# KeyboardMoudle2.net
KiCad netlist of a schematic drawn in Altium Designer
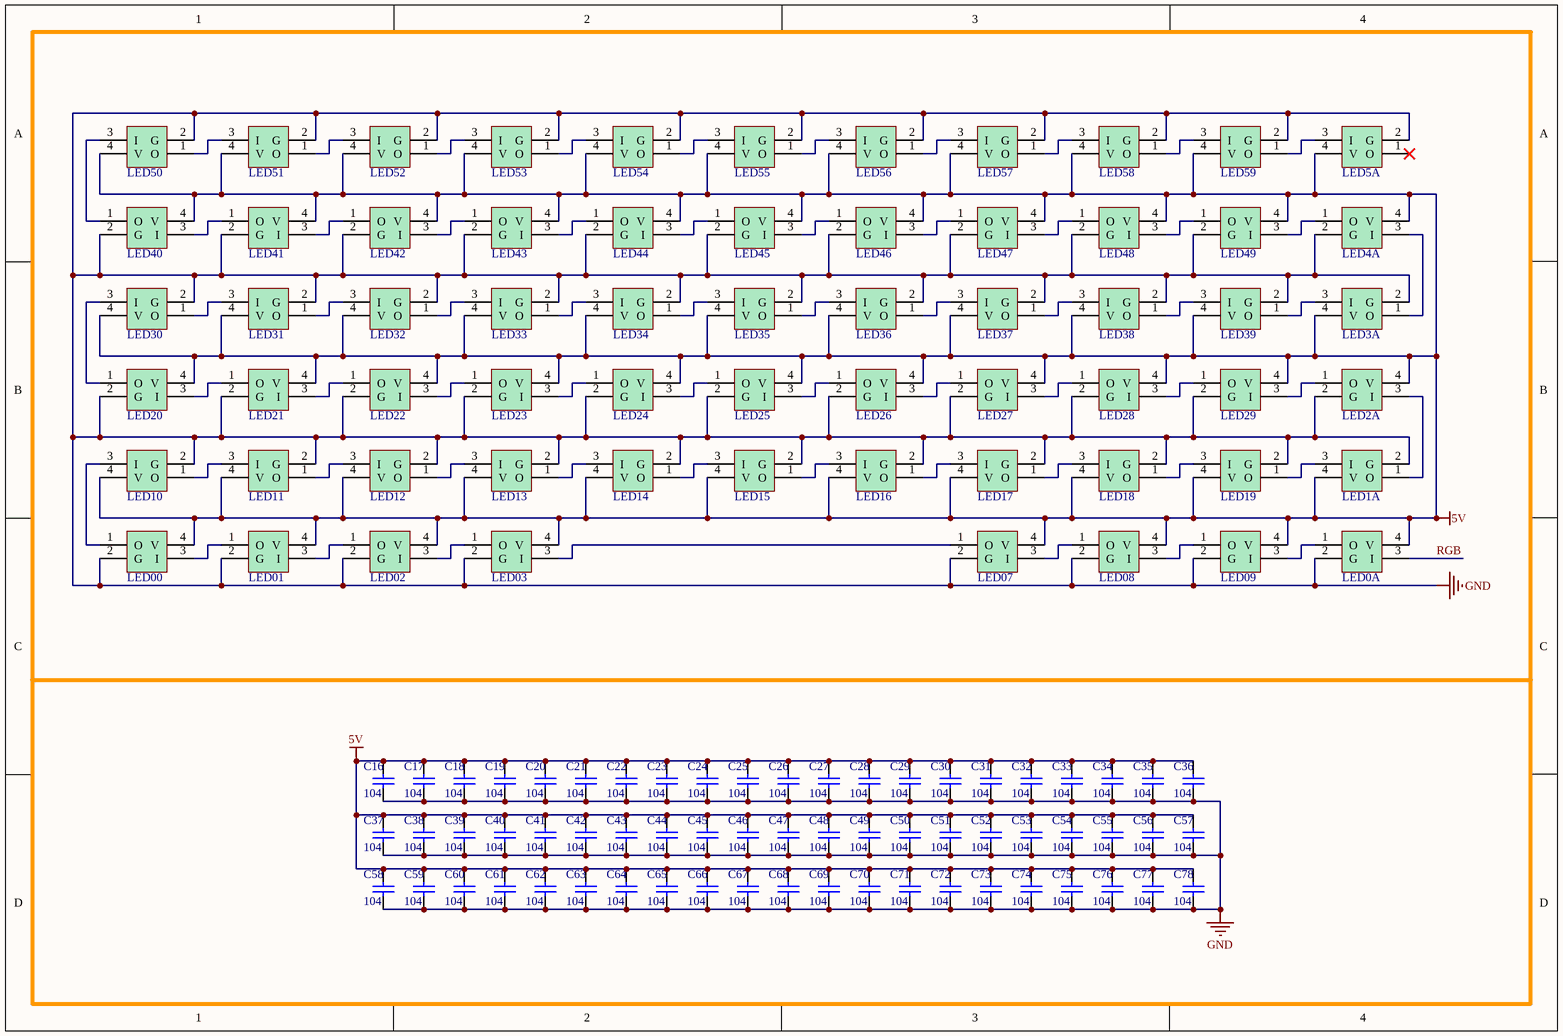
[diagram p0: KeyboardMoudle2.SchDoc]

(export (version "E")
  (design (tool "Eeschema 10.0.6"))
  (components
    (comp (ref "C16")
      (value "104")
      (footprint "0603")
      (description "贴片电容 0603")
      (libsource (lib "MT_Device") (part "CAP_0603"))
    )
    (comp (ref "C17")
      (value "104")
      (footprint "0603")
      (description "贴片电容 0603")
      (libsource (lib "MT_Device") (part "CAP_0603"))
    )
    (comp (ref "C18")
      (value "104")
      (footprint "0603")
      (description "贴片电容 0603")
      (libsource (lib "MT_Device") (part "CAP_0603"))
    )
    (comp (ref "C19")
      (value "104")
      (footprint "0603")
      (description "贴片电容 0603")
      (libsource (lib "MT_Device") (part "CAP_0603"))
    )
    (comp (ref "C20")
      (value "104")
      (footprint "0603")
      (description "贴片电容 0603")
      (libsource (lib "MT_Device") (part "CAP_0603"))
    )
    (comp (ref "C21")
      (value "104")
      (footprint "0603")
      (description "贴片电容 0603")
      (libsource (lib "MT_Device") (part "CAP_0603"))
    )
    (comp (ref "C22")
      (value "104")
      (footprint "0603")
      (description "贴片电容 0603")
      (libsource (lib "MT_Device") (part "CAP_0603"))
    )
    (comp (ref "C23")
      (value "104")
      (footprint "0603")
      (description "贴片电容 0603")
      (libsource (lib "MT_Device") (part "CAP_0603"))
    )
    (comp (ref "C24")
      (value "104")
      (footprint "0603")
      (description "贴片电容 0603")
      (libsource (lib "MT_Device") (part "CAP_0603"))
    )
    (comp (ref "C25")
      (value "104")
      (footprint "0603")
      (description "贴片电容 0603")
      (libsource (lib "MT_Device") (part "CAP_0603"))
    )
    (comp (ref "C26")
      (value "104")
      (footprint "0603")
      (description "贴片电容 0603")
      (libsource (lib "MT_Device") (part "CAP_0603"))
    )
    (comp (ref "C27")
      (value "104")
      (footprint "0603")
      (description "贴片电容 0603")
      (libsource (lib "MT_Device") (part "CAP_0603"))
    )
    (comp (ref "C28")
      (value "104")
      (footprint "0603")
      (description "贴片电容 0603")
      (libsource (lib "MT_Device") (part "CAP_0603"))
    )
    (comp (ref "C29")
      (value "104")
      (footprint "0603")
      (description "贴片电容 0603")
      (libsource (lib "MT_Device") (part "CAP_0603"))
    )
    (comp (ref "C30")
      (value "104")
      (footprint "0603")
      (description "贴片电容 0603")
      (libsource (lib "MT_Device") (part "CAP_0603"))
    )
    (comp (ref "C31")
      (value "104")
      (footprint "0603")
      (description "贴片电容 0603")
      (libsource (lib "MT_Device") (part "CAP_0603"))
    )
    (comp (ref "C32")
      (value "104")
      (footprint "0603")
      (description "贴片电容 0603")
      (libsource (lib "MT_Device") (part "CAP_0603"))
    )
    (comp (ref "C33")
      (value "104")
      (footprint "0603")
      (description "贴片电容 0603")
      (libsource (lib "MT_Device") (part "CAP_0603"))
    )
    (comp (ref "C34")
      (value "104")
      (footprint "0603")
      (description "贴片电容 0603")
      (libsource (lib "MT_Device") (part "CAP_0603"))
    )
    (comp (ref "C35")
      (value "104")
      (footprint "0603")
      (description "贴片电容 0603")
      (libsource (lib "MT_Device") (part "CAP_0603"))
    )
    (comp (ref "C36")
      (value "104")
      (footprint "0603")
      (description "贴片电容 0603")
      (libsource (lib "MT_Device") (part "CAP_0603"))
    )
    (comp (ref "C37")
      (value "104")
      (footprint "0603")
      (description "贴片电容 0603")
      (libsource (lib "MT_Device") (part "CAP_0603"))
    )
    (comp (ref "C38")
      (value "104")
      (footprint "0603")
      (description "贴片电容 0603")
      (libsource (lib "MT_Device") (part "CAP_0603"))
    )
    (comp (ref "C39")
      (value "104")
      (footprint "0603")
      (description "贴片电容 0603")
      (libsource (lib "MT_Device") (part "CAP_0603"))
    )
    (comp (ref "C40")
      (value "104")
      (footprint "0603")
      (description "贴片电容 0603")
      (libsource (lib "MT_Device") (part "CAP_0603"))
    )
    (comp (ref "C41")
      (value "104")
      (footprint "0603")
      (description "贴片电容 0603")
      (libsource (lib "MT_Device") (part "CAP_0603"))
    )
    (comp (ref "C42")
      (value "104")
      (footprint "0603")
      (description "贴片电容 0603")
      (libsource (lib "MT_Device") (part "CAP_0603"))
    )
    (comp (ref "C43")
      (value "104")
      (footprint "0603")
      (description "贴片电容 0603")
      (libsource (lib "MT_Device") (part "CAP_0603"))
    )
    (comp (ref "C44")
      (value "104")
      (footprint "0603")
      (description "贴片电容 0603")
      (libsource (lib "MT_Device") (part "CAP_0603"))
    )
    (comp (ref "C45")
      (value "104")
      (footprint "0603")
      (description "贴片电容 0603")
      (libsource (lib "MT_Device") (part "CAP_0603"))
    )
    (comp (ref "C46")
      (value "104")
      (footprint "0603")
      (description "贴片电容 0603")
      (libsource (lib "MT_Device") (part "CAP_0603"))
    )
    (comp (ref "C47")
      (value "104")
      (footprint "0603")
      (description "贴片电容 0603")
      (libsource (lib "MT_Device") (part "CAP_0603"))
    )
    (comp (ref "C48")
      (value "104")
      (footprint "0603")
      (description "贴片电容 0603")
      (libsource (lib "MT_Device") (part "CAP_0603"))
    )
    (comp (ref "C49")
      (value "104")
      (footprint "0603")
      (description "贴片电容 0603")
      (libsource (lib "MT_Device") (part "CAP_0603"))
    )
    (comp (ref "C50")
      (value "104")
      (footprint "0603")
      (description "贴片电容 0603")
      (libsource (lib "MT_Device") (part "CAP_0603"))
    )
    (comp (ref "C51")
      (value "104")
      (footprint "0603")
      (description "贴片电容 0603")
      (libsource (lib "MT_Device") (part "CAP_0603"))
    )
    (comp (ref "C52")
      (value "104")
      (footprint "0603")
      (description "贴片电容 0603")
      (libsource (lib "MT_Device") (part "CAP_0603"))
    )
    (comp (ref "C53")
      (value "104")
      (footprint "0603")
      (description "贴片电容 0603")
      (libsource (lib "MT_Device") (part "CAP_0603"))
    )
    (comp (ref "C54")
      (value "104")
      (footprint "0603")
      (description "贴片电容 0603")
      (libsource (lib "MT_Device") (part "CAP_0603"))
    )
    (comp (ref "C55")
      (value "104")
      (footprint "0603")
      (description "贴片电容 0603")
      (libsource (lib "MT_Device") (part "CAP_0603"))
    )
    (comp (ref "C56")
      (value "104")
      (footprint "0603")
      (description "贴片电容 0603")
      (libsource (lib "MT_Device") (part "CAP_0603"))
    )
    (comp (ref "C57")
      (value "104")
      (footprint "0603")
      (description "贴片电容 0603")
      (libsource (lib "MT_Device") (part "CAP_0603"))
    )
    (comp (ref "C58")
      (value "104")
      (footprint "0603")
      (description "贴片电容 0603")
      (libsource (lib "MT_Device") (part "CAP_0603"))
    )
    (comp (ref "C59")
      (value "104")
      (footprint "0603")
      (description "贴片电容 0603")
      (libsource (lib "MT_Device") (part "CAP_0603"))
    )
    (comp (ref "C60")
      (value "104")
      (footprint "0603")
      (description "贴片电容 0603")
      (libsource (lib "MT_Device") (part "CAP_0603"))
    )
    (comp (ref "C61")
      (value "104")
      (footprint "0603")
      (description "贴片电容 0603")
      (libsource (lib "MT_Device") (part "CAP_0603"))
    )
    (comp (ref "C62")
      (value "104")
      (footprint "0603")
      (description "贴片电容 0603")
      (libsource (lib "MT_Device") (part "CAP_0603"))
    )
    (comp (ref "C63")
      (value "104")
      (footprint "0603")
      (description "贴片电容 0603")
      (libsource (lib "MT_Device") (part "CAP_0603"))
    )
    (comp (ref "C64")
      (value "104")
      (footprint "0603")
      (description "贴片电容 0603")
      (libsource (lib "MT_Device") (part "CAP_0603"))
    )
    (comp (ref "C65")
      (value "104")
      (footprint "0603")
      (description "贴片电容 0603")
      (libsource (lib "MT_Device") (part "CAP_0603"))
    )
    (comp (ref "C66")
      (value "104")
      (footprint "0603")
      (description "贴片电容 0603")
      (libsource (lib "MT_Device") (part "CAP_0603"))
    )
    (comp (ref "C67")
      (value "104")
      (footprint "0603")
      (description "贴片电容 0603")
      (libsource (lib "MT_Device") (part "CAP_0603"))
    )
    (comp (ref "C68")
      (value "104")
      (footprint "0603")
      (description "贴片电容 0603")
      (libsource (lib "MT_Device") (part "CAP_0603"))
    )
    (comp (ref "C69")
      (value "104")
      (footprint "0603")
      (description "贴片电容 0603")
      (libsource (lib "MT_Device") (part "CAP_0603"))
    )
    (comp (ref "C70")
      (value "104")
      (footprint "0603")
      (description "贴片电容 0603")
      (libsource (lib "MT_Device") (part "CAP_0603"))
    )
    (comp (ref "C71")
      (value "104")
      (footprint "0603")
      (description "贴片电容 0603")
      (libsource (lib "MT_Device") (part "CAP_0603"))
    )
    (comp (ref "C72")
      (value "104")
      (footprint "0603")
      (description "贴片电容 0603")
      (libsource (lib "MT_Device") (part "CAP_0603"))
    )
    (comp (ref "C73")
      (value "104")
      (footprint "0603")
      (description "贴片电容 0603")
      (libsource (lib "MT_Device") (part "CAP_0603"))
    )
    (comp (ref "C74")
      (value "104")
      (footprint "0603")
      (description "贴片电容 0603")
      (libsource (lib "MT_Device") (part "CAP_0603"))
    )
    (comp (ref "C75")
      (value "104")
      (footprint "0603")
      (description "贴片电容 0603")
      (libsource (lib "MT_Device") (part "CAP_0603"))
    )
    (comp (ref "C76")
      (value "104")
      (footprint "0603")
      (description "贴片电容 0603")
      (libsource (lib "MT_Device") (part "CAP_0603"))
    )
    (comp (ref "C77")
      (value "104")
      (footprint "0603")
      (description "贴片电容 0603")
      (libsource (lib "MT_Device") (part "CAP_0603"))
    )
    (comp (ref "C78")
      (value "104")
      (footprint "0603")
      (description "贴片电容 0603")
      (libsource (lib "MT_Device") (part "CAP_0603"))
    )
    (comp (ref "LED00")
      (value "WS2812")
      (footprint "LED_WS2812_2020")
      (description "WS2812 LED")
      (libsource (lib "") (part "LED_WS2812_2020_1"))
    )
    (comp (ref "LED0A")
      (value "WS2812")
      (footprint "LED_WS2812_2020")
      (description "WS2812 LED")
      (libsource (lib "") (part "LED_WS2812_2020_1"))
    )
    (comp (ref "LED01")
      (value "WS2812")
      (footprint "LED_WS2812_2020")
      (description "WS2812 LED")
      (libsource (lib "") (part "LED_WS2812_2020_1"))
    )
    (comp (ref "LED1A")
      (value "WS2812")
      (footprint "LED_WS2812_2020")
      (description "WS2812 LED")
      (libsource (lib "MT_Device") (part "LED_WS2812_2020"))
    )
    (comp (ref "LED02")
      (value "WS2812")
      (footprint "LED_WS2812_2020")
      (description "WS2812 LED")
      (libsource (lib "") (part "LED_WS2812_2020_1"))
    )
    (comp (ref "LED2A")
      (value "WS2812")
      (footprint "LED_WS2812_2020")
      (description "WS2812 LED")
      (libsource (lib "") (part "LED_WS2812_2020_1"))
    )
    (comp (ref "LED03")
      (value "WS2812")
      (footprint "LED_WS2812_2020")
      (description "WS2812 LED")
      (libsource (lib "") (part "LED_WS2812_2020_1"))
    )
    (comp (ref "LED3A")
      (value "WS2812")
      (footprint "LED_WS2812_2020")
      (description "WS2812 LED")
      (libsource (lib "MT_Device") (part "LED_WS2812_2020"))
    )
    (comp (ref "LED4A")
      (value "WS2812")
      (footprint "LED_WS2812_2020")
      (description "WS2812 LED")
      (libsource (lib "") (part "LED_WS2812_2020_1"))
    )
    (comp (ref "LED5A")
      (value "WS2812")
      (footprint "LED_WS2812_2020")
      (description "WS2812 LED")
      (libsource (lib "MT_Device") (part "LED_WS2812_2020"))
    )
    (comp (ref "LED07")
      (value "WS2812")
      (footprint "LED_WS2812_2020")
      (description "WS2812 LED")
      (libsource (lib "") (part "LED_WS2812_2020_1"))
    )
    (comp (ref "LED08")
      (value "WS2812")
      (footprint "LED_WS2812_2020")
      (description "WS2812 LED")
      (libsource (lib "") (part "LED_WS2812_2020_1"))
    )
    (comp (ref "LED09")
      (value "WS2812")
      (footprint "LED_WS2812_2020")
      (description "WS2812 LED")
      (libsource (lib "") (part "LED_WS2812_2020_1"))
    )
    (comp (ref "LED10")
      (value "WS2812")
      (footprint "LED_WS2812_2020")
      (description "WS2812 LED")
      (libsource (lib "MT_Device") (part "LED_WS2812_2020"))
    )
    (comp (ref "LED11")
      (value "WS2812")
      (footprint "LED_WS2812_2020")
      (description "WS2812 LED")
      (libsource (lib "MT_Device") (part "LED_WS2812_2020"))
    )
    (comp (ref "LED12")
      (value "WS2812")
      (footprint "LED_WS2812_2020")
      (description "WS2812 LED")
      (libsource (lib "MT_Device") (part "LED_WS2812_2020"))
    )
    (comp (ref "LED13")
      (value "WS2812")
      (footprint "LED_WS2812_2020")
      (description "WS2812 LED")
      (libsource (lib "MT_Device") (part "LED_WS2812_2020"))
    )
    (comp (ref "LED14")
      (value "WS2812")
      (footprint "LED_WS2812_2020")
      (description "WS2812 LED")
      (libsource (lib "MT_Device") (part "LED_WS2812_2020"))
    )
    (comp (ref "LED15")
      (value "WS2812")
      (footprint "LED_WS2812_2020")
      (description "WS2812 LED")
      (libsource (lib "MT_Device") (part "LED_WS2812_2020"))
    )
    (comp (ref "LED16")
      (value "WS2812")
      (footprint "LED_WS2812_2020")
      (description "WS2812 LED")
      (libsource (lib "MT_Device") (part "LED_WS2812_2020"))
    )
    (comp (ref "LED17")
      (value "WS2812")
      (footprint "LED_WS2812_2020")
      (description "WS2812 LED")
      (libsource (lib "MT_Device") (part "LED_WS2812_2020"))
    )
    (comp (ref "LED18")
      (value "WS2812")
      (footprint "LED_WS2812_2020")
      (description "WS2812 LED")
      (libsource (lib "MT_Device") (part "LED_WS2812_2020"))
    )
    (comp (ref "LED19")
      (value "WS2812")
      (footprint "LED_WS2812_2020")
      (description "WS2812 LED")
      (libsource (lib "MT_Device") (part "LED_WS2812_2020"))
    )
    (comp (ref "LED20")
      (value "WS2812")
      (footprint "LED_WS2812_2020")
      (description "WS2812 LED")
      (libsource (lib "") (part "LED_WS2812_2020_1"))
    )
    (comp (ref "LED21")
      (value "WS2812")
      (footprint "LED_WS2812_2020")
      (description "WS2812 LED")
      (libsource (lib "") (part "LED_WS2812_2020_1"))
    )
    (comp (ref "LED22")
      (value "WS2812")
      (footprint "LED_WS2812_2020")
      (description "WS2812 LED")
      (libsource (lib "") (part "LED_WS2812_2020_1"))
    )
    (comp (ref "LED23")
      (value "WS2812")
      (footprint "LED_WS2812_2020")
      (description "WS2812 LED")
      (libsource (lib "") (part "LED_WS2812_2020_1"))
    )
    (comp (ref "LED24")
      (value "WS2812")
      (footprint "LED_WS2812_2020")
      (description "WS2812 LED")
      (libsource (lib "") (part "LED_WS2812_2020_1"))
    )
    (comp (ref "LED25")
      (value "WS2812")
      (footprint "LED_WS2812_2020")
      (description "WS2812 LED")
      (libsource (lib "") (part "LED_WS2812_2020_1"))
    )
    (comp (ref "LED26")
      (value "WS2812")
      (footprint "LED_WS2812_2020")
      (description "WS2812 LED")
      (libsource (lib "") (part "LED_WS2812_2020_1"))
    )
    (comp (ref "LED27")
      (value "WS2812")
      (footprint "LED_WS2812_2020")
      (description "WS2812 LED")
      (libsource (lib "") (part "LED_WS2812_2020_1"))
    )
    (comp (ref "LED28")
      (value "WS2812")
      (footprint "LED_WS2812_2020")
      (description "WS2812 LED")
      (libsource (lib "") (part "LED_WS2812_2020_1"))
    )
    (comp (ref "LED29")
      (value "WS2812")
      (footprint "LED_WS2812_2020")
      (description "WS2812 LED")
      (libsource (lib "") (part "LED_WS2812_2020_1"))
    )
    (comp (ref "LED30")
      (value "WS2812")
      (footprint "LED_WS2812_2020")
      (description "WS2812 LED")
      (libsource (lib "MT_Device") (part "LED_WS2812_2020"))
    )
    (comp (ref "LED31")
      (value "WS2812")
      (footprint "LED_WS2812_2020")
      (description "WS2812 LED")
      (libsource (lib "MT_Device") (part "LED_WS2812_2020"))
    )
    (comp (ref "LED32")
      (value "WS2812")
      (footprint "LED_WS2812_2020")
      (description "WS2812 LED")
      (libsource (lib "MT_Device") (part "LED_WS2812_2020"))
    )
    (comp (ref "LED33")
      (value "WS2812")
      (footprint "LED_WS2812_2020")
      (description "WS2812 LED")
      (libsource (lib "MT_Device") (part "LED_WS2812_2020"))
    )
    (comp (ref "LED34")
      (value "WS2812")
      (footprint "LED_WS2812_2020")
      (description "WS2812 LED")
      (libsource (lib "MT_Device") (part "LED_WS2812_2020"))
    )
    (comp (ref "LED35")
      (value "WS2812")
      (footprint "LED_WS2812_2020")
      (description "WS2812 LED")
      (libsource (lib "MT_Device") (part "LED_WS2812_2020"))
    )
    (comp (ref "LED36")
      (value "WS2812")
      (footprint "LED_WS2812_2020")
      (description "WS2812 LED")
      (libsource (lib "MT_Device") (part "LED_WS2812_2020"))
    )
    (comp (ref "LED37")
      (value "WS2812")
      (footprint "LED_WS2812_2020")
      (description "WS2812 LED")
      (libsource (lib "MT_Device") (part "LED_WS2812_2020"))
    )
    (comp (ref "LED38")
      (value "WS2812")
      (footprint "LED_WS2812_2020")
      (description "WS2812 LED")
      (libsource (lib "MT_Device") (part "LED_WS2812_2020"))
    )
    (comp (ref "LED39")
      (value "WS2812")
      (footprint "LED_WS2812_2020")
      (description "WS2812 LED")
      (libsource (lib "MT_Device") (part "LED_WS2812_2020"))
    )
    (comp (ref "LED40")
      (value "WS2812")
      (footprint "LED_WS2812_2020")
      (description "WS2812 LED")
      (libsource (lib "") (part "LED_WS2812_2020_1"))
    )
    (comp (ref "LED41")
      (value "WS2812")
      (footprint "LED_WS2812_2020")
      (description "WS2812 LED")
      (libsource (lib "") (part "LED_WS2812_2020_1"))
    )
    (comp (ref "LED42")
      (value "WS2812")
      (footprint "LED_WS2812_2020")
      (description "WS2812 LED")
      (libsource (lib "") (part "LED_WS2812_2020_1"))
    )
    (comp (ref "LED43")
      (value "WS2812")
      (footprint "LED_WS2812_2020")
      (description "WS2812 LED")
      (libsource (lib "") (part "LED_WS2812_2020_1"))
    )
    (comp (ref "LED44")
      (value "WS2812")
      (footprint "LED_WS2812_2020")
      (description "WS2812 LED")
      (libsource (lib "") (part "LED_WS2812_2020_1"))
    )
    (comp (ref "LED45")
      (value "WS2812")
      (footprint "LED_WS2812_2020")
      (description "WS2812 LED")
      (libsource (lib "") (part "LED_WS2812_2020_1"))
    )
    (comp (ref "LED46")
      (value "WS2812")
      (footprint "LED_WS2812_2020")
      (description "WS2812 LED")
      (libsource (lib "") (part "LED_WS2812_2020_1"))
    )
    (comp (ref "LED47")
      (value "WS2812")
      (footprint "LED_WS2812_2020")
      (description "WS2812 LED")
      (libsource (lib "") (part "LED_WS2812_2020_1"))
    )
    (comp (ref "LED48")
      (value "WS2812")
      (footprint "LED_WS2812_2020")
      (description "WS2812 LED")
      (libsource (lib "") (part "LED_WS2812_2020_1"))
    )
    (comp (ref "LED49")
      (value "WS2812")
      (footprint "LED_WS2812_2020")
      (description "WS2812 LED")
      (libsource (lib "") (part "LED_WS2812_2020_1"))
    )
    (comp (ref "LED50")
      (value "WS2812")
      (footprint "LED_WS2812_2020")
      (description "WS2812 LED")
      (libsource (lib "MT_Device") (part "LED_WS2812_2020"))
    )
    (comp (ref "LED51")
      (value "WS2812")
      (footprint "LED_WS2812_2020")
      (description "WS2812 LED")
      (libsource (lib "MT_Device") (part "LED_WS2812_2020"))
    )
    (comp (ref "LED52")
      (value "WS2812")
      (footprint "LED_WS2812_2020")
      (description "WS2812 LED")
      (libsource (lib "MT_Device") (part "LED_WS2812_2020"))
    )
    (comp (ref "LED53")
      (value "WS2812")
      (footprint "LED_WS2812_2020")
      (description "WS2812 LED")
      (libsource (lib "MT_Device") (part "LED_WS2812_2020"))
    )
    (comp (ref "LED54")
      (value "WS2812")
      (footprint "LED_WS2812_2020")
      (description "WS2812 LED")
      (libsource (lib "MT_Device") (part "LED_WS2812_2020"))
    )
    (comp (ref "LED55")
      (value "WS2812")
      (footprint "LED_WS2812_2020")
      (description "WS2812 LED")
      (libsource (lib "MT_Device") (part "LED_WS2812_2020"))
    )
    (comp (ref "LED56")
      (value "WS2812")
      (footprint "LED_WS2812_2020")
      (description "WS2812 LED")
      (libsource (lib "MT_Device") (part "LED_WS2812_2020"))
    )
    (comp (ref "LED57")
      (value "WS2812")
      (footprint "LED_WS2812_2020")
      (description "WS2812 LED")
      (libsource (lib "MT_Device") (part "LED_WS2812_2020"))
    )
    (comp (ref "LED58")
      (value "WS2812")
      (footprint "LED_WS2812_2020")
      (description "WS2812 LED")
      (libsource (lib "MT_Device") (part "LED_WS2812_2020"))
    )
    (comp (ref "LED59")
      (value "WS2812")
      (footprint "LED_WS2812_2020")
      (description "WS2812 LED")
      (libsource (lib "MT_Device") (part "LED_WS2812_2020"))
    )
  )
  (nets
    (net (code "1") (name "/RGB") (class "Default")
      (node (ref "LED0A") (pin "3") (pinfunction "I_3") (pintype "passive"))
    )
    (net (code "2") (name "5V") (class "Default")
      (node (ref "C16") (pin "2") (pinfunction "2_2") (pintype "passive"))
      (node (ref "C17") (pin "2") (pinfunction "2_2") (pintype "passive"))
      (node (ref "C18") (pin "2") (pinfunction "2_2") (pintype "passive"))
      (node (ref "C19") (pin "2") (pinfunction "2_2") (pintype "passive"))
      (node (ref "C20") (pin "2") (pinfunction "2_2") (pintype "passive"))
      (node (ref "C21") (pin "2") (pinfunction "2_2") (pintype "passive"))
      (node (ref "C22") (pin "2") (pinfunction "2_2") (pintype "passive"))
      (node (ref "C23") (pin "2") (pinfunction "2_2") (pintype "passive"))
      (node (ref "C24") (pin "2") (pinfunction "2_2") (pintype "passive"))
      (node (ref "C25") (pin "2") (pinfunction "2_2") (pintype "passive"))
      (node (ref "C26") (pin "2") (pinfunction "2_2") (pintype "passive"))
      (node (ref "C27") (pin "2") (pinfunction "2_2") (pintype "passive"))
      (node (ref "C28") (pin "2") (pinfunction "2_2") (pintype "passive"))
      (node (ref "C29") (pin "2") (pinfunction "2_2") (pintype "passive"))
      (node (ref "C30") (pin "2") (pinfunction "2_2") (pintype "passive"))
      (node (ref "C31") (pin "2") (pinfunction "2_2") (pintype "passive"))
      (node (ref "C32") (pin "2") (pinfunction "2_2") (pintype "passive"))
      (node (ref "C33") (pin "2") (pinfunction "2_2") (pintype "passive"))
      (node (ref "C34") (pin "2") (pinfunction "2_2") (pintype "passive"))
      (node (ref "C35") (pin "2") (pinfunction "2_2") (pintype "passive"))
      (node (ref "C36") (pin "2") (pinfunction "2_2") (pintype "passive"))
      (node (ref "C37") (pin "2") (pinfunction "2_2") (pintype "passive"))
      (node (ref "C38") (pin "2") (pinfunction "2_2") (pintype "passive"))
      (node (ref "C39") (pin "2") (pinfunction "2_2") (pintype "passive"))
      (node (ref "C40") (pin "2") (pinfunction "2_2") (pintype "passive"))
      (node (ref "C41") (pin "2") (pinfunction "2_2") (pintype "passive"))
      (node (ref "C42") (pin "2") (pinfunction "2_2") (pintype "passive"))
      (node (ref "C43") (pin "2") (pinfunction "2_2") (pintype "passive"))
      (node (ref "C44") (pin "2") (pinfunction "2_2") (pintype "passive"))
      (node (ref "C45") (pin "2") (pinfunction "2_2") (pintype "passive"))
      (node (ref "C46") (pin "2") (pinfunction "2_2") (pintype "passive"))
      (node (ref "C47") (pin "2") (pinfunction "2_2") (pintype "passive"))
      (node (ref "C48") (pin "2") (pinfunction "2_2") (pintype "passive"))
      (node (ref "C49") (pin "2") (pinfunction "2_2") (pintype "passive"))
      (node (ref "C50") (pin "2") (pinfunction "2_2") (pintype "passive"))
      (node (ref "C51") (pin "2") (pinfunction "2_2") (pintype "passive"))
      (node (ref "C52") (pin "2") (pinfunction "2_2") (pintype "passive"))
      (node (ref "C53") (pin "2") (pinfunction "2_2") (pintype "passive"))
      (node (ref "C54") (pin "2") (pinfunction "2_2") (pintype "passive"))
      (node (ref "C55") (pin "2") (pinfunction "2_2") (pintype "passive"))
      (node (ref "C56") (pin "2") (pinfunction "2_2") (pintype "passive"))
      (node (ref "C57") (pin "2") (pinfunction "2_2") (pintype "passive"))
      (node (ref "C58") (pin "2") (pinfunction "2_2") (pintype "passive"))
      (node (ref "C59") (pin "2") (pinfunction "2_2") (pintype "passive"))
      (node (ref "C60") (pin "2") (pinfunction "2_2") (pintype "passive"))
      (node (ref "C61") (pin "2") (pinfunction "2_2") (pintype "passive"))
      (node (ref "C62") (pin "2") (pinfunction "2_2") (pintype "passive"))
      (node (ref "C63") (pin "2") (pinfunction "2_2") (pintype "passive"))
      (node (ref "C64") (pin "2") (pinfunction "2_2") (pintype "passive"))
      (node (ref "C65") (pin "2") (pinfunction "2_2") (pintype "passive"))
      (node (ref "C66") (pin "2") (pinfunction "2_2") (pintype "passive"))
      (node (ref "C67") (pin "2") (pinfunction "2_2") (pintype "passive"))
      (node (ref "C68") (pin "2") (pinfunction "2_2") (pintype "passive"))
      (node (ref "C69") (pin "2") (pinfunction "2_2") (pintype "passive"))
      (node (ref "C70") (pin "2") (pinfunction "2_2") (pintype "passive"))
      (node (ref "C71") (pin "2") (pinfunction "2_2") (pintype "passive"))
      (node (ref "C72") (pin "2") (pinfunction "2_2") (pintype "passive"))
      (node (ref "C73") (pin "2") (pinfunction "2_2") (pintype "passive"))
      (node (ref "C74") (pin "2") (pinfunction "2_2") (pintype "passive"))
      (node (ref "C75") (pin "2") (pinfunction "2_2") (pintype "passive"))
      (node (ref "C76") (pin "2") (pinfunction "2_2") (pintype "passive"))
      (node (ref "C77") (pin "2") (pinfunction "2_2") (pintype "passive"))
      (node (ref "C78") (pin "2") (pinfunction "2_2") (pintype "passive"))
      (node (ref "LED00") (pin "4") (pinfunction "V_4") (pintype "passive"))
      (node (ref "LED01") (pin "4") (pinfunction "V_4") (pintype "passive"))
      (node (ref "LED02") (pin "4") (pinfunction "V_4") (pintype "passive"))
      (node (ref "LED03") (pin "4") (pinfunction "V_4") (pintype "passive"))
      (node (ref "LED07") (pin "4") (pinfunction "V_4") (pintype "passive"))
      (node (ref "LED08") (pin "4") (pinfunction "V_4") (pintype "passive"))
      (node (ref "LED09") (pin "4") (pinfunction "V_4") (pintype "passive"))
      (node (ref "LED0A") (pin "4") (pinfunction "V_4") (pintype "passive"))
      (node (ref "LED10") (pin "4") (pinfunction "V_4") (pintype "passive"))
      (node (ref "LED11") (pin "4") (pinfunction "V_4") (pintype "passive"))
      (node (ref "LED12") (pin "4") (pinfunction "V_4") (pintype "passive"))
      (node (ref "LED13") (pin "4") (pinfunction "V_4") (pintype "passive"))
      (node (ref "LED14") (pin "4") (pinfunction "V_4") (pintype "passive"))
      (node (ref "LED15") (pin "4") (pinfunction "V_4") (pintype "passive"))
      (node (ref "LED16") (pin "4") (pinfunction "V_4") (pintype "passive"))
      (node (ref "LED17") (pin "4") (pinfunction "V_4") (pintype "passive"))
      (node (ref "LED18") (pin "4") (pinfunction "V_4") (pintype "passive"))
      (node (ref "LED19") (pin "4") (pinfunction "V_4") (pintype "passive"))
      (node (ref "LED1A") (pin "4") (pinfunction "V_4") (pintype "passive"))
      (node (ref "LED20") (pin "4") (pinfunction "V_4") (pintype "passive"))
      (node (ref "LED21") (pin "4") (pinfunction "V_4") (pintype "passive"))
      (node (ref "LED22") (pin "4") (pinfunction "V_4") (pintype "passive"))
      (node (ref "LED23") (pin "4") (pinfunction "V_4") (pintype "passive"))
      (node (ref "LED24") (pin "4") (pinfunction "V_4") (pintype "passive"))
      (node (ref "LED25") (pin "4") (pinfunction "V_4") (pintype "passive"))
      (node (ref "LED26") (pin "4") (pinfunction "V_4") (pintype "passive"))
      (node (ref "LED27") (pin "4") (pinfunction "V_4") (pintype "passive"))
      (node (ref "LED28") (pin "4") (pinfunction "V_4") (pintype "passive"))
      (node (ref "LED29") (pin "4") (pinfunction "V_4") (pintype "passive"))
      (node (ref "LED2A") (pin "4") (pinfunction "V_4") (pintype "passive"))
      (node (ref "LED30") (pin "4") (pinfunction "V_4") (pintype "passive"))
      (node (ref "LED31") (pin "4") (pinfunction "V_4") (pintype "passive"))
      (node (ref "LED32") (pin "4") (pinfunction "V_4") (pintype "passive"))
      (node (ref "LED33") (pin "4") (pinfunction "V_4") (pintype "passive"))
      (node (ref "LED34") (pin "4") (pinfunction "V_4") (pintype "passive"))
      (node (ref "LED35") (pin "4") (pinfunction "V_4") (pintype "passive"))
      (node (ref "LED36") (pin "4") (pinfunction "V_4") (pintype "passive"))
      (node (ref "LED37") (pin "4") (pinfunction "V_4") (pintype "passive"))
      (node (ref "LED38") (pin "4") (pinfunction "V_4") (pintype "passive"))
      (node (ref "LED39") (pin "4") (pinfunction "V_4") (pintype "passive"))
      (node (ref "LED3A") (pin "4") (pinfunction "V_4") (pintype "passive"))
      (node (ref "LED40") (pin "4") (pinfunction "V_4") (pintype "passive"))
      (node (ref "LED41") (pin "4") (pinfunction "V_4") (pintype "passive"))
      (node (ref "LED42") (pin "4") (pinfunction "V_4") (pintype "passive"))
      (node (ref "LED43") (pin "4") (pinfunction "V_4") (pintype "passive"))
      (node (ref "LED44") (pin "4") (pinfunction "V_4") (pintype "passive"))
      (node (ref "LED45") (pin "4") (pinfunction "V_4") (pintype "passive"))
      (node (ref "LED46") (pin "4") (pinfunction "V_4") (pintype "passive"))
      (node (ref "LED47") (pin "4") (pinfunction "V_4") (pintype "passive"))
      (node (ref "LED48") (pin "4") (pinfunction "V_4") (pintype "passive"))
      (node (ref "LED49") (pin "4") (pinfunction "V_4") (pintype "passive"))
      (node (ref "LED4A") (pin "4") (pinfunction "V_4") (pintype "passive"))
      (node (ref "LED50") (pin "4") (pinfunction "V_4") (pintype "passive"))
      (node (ref "LED51") (pin "4") (pinfunction "V_4") (pintype "passive"))
      (node (ref "LED52") (pin "4") (pinfunction "V_4") (pintype "passive"))
      (node (ref "LED53") (pin "4") (pinfunction "V_4") (pintype "passive"))
      (node (ref "LED54") (pin "4") (pinfunction "V_4") (pintype "passive"))
      (node (ref "LED55") (pin "4") (pinfunction "V_4") (pintype "passive"))
      (node (ref "LED56") (pin "4") (pinfunction "V_4") (pintype "passive"))
      (node (ref "LED57") (pin "4") (pinfunction "V_4") (pintype "passive"))
      (node (ref "LED58") (pin "4") (pinfunction "V_4") (pintype "passive"))
      (node (ref "LED59") (pin "4") (pinfunction "V_4") (pintype "passive"))
      (node (ref "LED5A") (pin "4") (pinfunction "V_4") (pintype "passive"))
    )
    (net (code "3") (name "GND") (class "Default")
      (node (ref "C16") (pin "1") (pinfunction "1_1") (pintype "passive"))
      (node (ref "C17") (pin "1") (pinfunction "1_1") (pintype "passive"))
      (node (ref "C18") (pin "1") (pinfunction "1_1") (pintype "passive"))
      (node (ref "C19") (pin "1") (pinfunction "1_1") (pintype "passive"))
      (node (ref "C20") (pin "1") (pinfunction "1_1") (pintype "passive"))
      (node (ref "C21") (pin "1") (pinfunction "1_1") (pintype "passive"))
      (node (ref "C22") (pin "1") (pinfunction "1_1") (pintype "passive"))
      (node (ref "C23") (pin "1") (pinfunction "1_1") (pintype "passive"))
      (node (ref "C24") (pin "1") (pinfunction "1_1") (pintype "passive"))
      (node (ref "C25") (pin "1") (pinfunction "1_1") (pintype "passive"))
      (node (ref "C26") (pin "1") (pinfunction "1_1") (pintype "passive"))
      (node (ref "C27") (pin "1") (pinfunction "1_1") (pintype "passive"))
      (node (ref "C28") (pin "1") (pinfunction "1_1") (pintype "passive"))
      (node (ref "C29") (pin "1") (pinfunction "1_1") (pintype "passive"))
      (node (ref "C30") (pin "1") (pinfunction "1_1") (pintype "passive"))
      (node (ref "C31") (pin "1") (pinfunction "1_1") (pintype "passive"))
      (node (ref "C32") (pin "1") (pinfunction "1_1") (pintype "passive"))
      (node (ref "C33") (pin "1") (pinfunction "1_1") (pintype "passive"))
      (node (ref "C34") (pin "1") (pinfunction "1_1") (pintype "passive"))
      (node (ref "C35") (pin "1") (pinfunction "1_1") (pintype "passive"))
      (node (ref "C36") (pin "1") (pinfunction "1_1") (pintype "passive"))
      (node (ref "C37") (pin "1") (pinfunction "1_1") (pintype "passive"))
      (node (ref "C38") (pin "1") (pinfunction "1_1") (pintype "passive"))
      (node (ref "C39") (pin "1") (pinfunction "1_1") (pintype "passive"))
      (node (ref "C40") (pin "1") (pinfunction "1_1") (pintype "passive"))
      (node (ref "C41") (pin "1") (pinfunction "1_1") (pintype "passive"))
      (node (ref "C42") (pin "1") (pinfunction "1_1") (pintype "passive"))
      (node (ref "C43") (pin "1") (pinfunction "1_1") (pintype "passive"))
      (node (ref "C44") (pin "1") (pinfunction "1_1") (pintype "passive"))
      (node (ref "C45") (pin "1") (pinfunction "1_1") (pintype "passive"))
      (node (ref "C46") (pin "1") (pinfunction "1_1") (pintype "passive"))
      (node (ref "C47") (pin "1") (pinfunction "1_1") (pintype "passive"))
      (node (ref "C48") (pin "1") (pinfunction "1_1") (pintype "passive"))
      (node (ref "C49") (pin "1") (pinfunction "1_1") (pintype "passive"))
      (node (ref "C50") (pin "1") (pinfunction "1_1") (pintype "passive"))
      (node (ref "C51") (pin "1") (pinfunction "1_1") (pintype "passive"))
      (node (ref "C52") (pin "1") (pinfunction "1_1") (pintype "passive"))
      (node (ref "C53") (pin "1") (pinfunction "1_1") (pintype "passive"))
      (node (ref "C54") (pin "1") (pinfunction "1_1") (pintype "passive"))
      (node (ref "C55") (pin "1") (pinfunction "1_1") (pintype "passive"))
      (node (ref "C56") (pin "1") (pinfunction "1_1") (pintype "passive"))
      (node (ref "C57") (pin "1") (pinfunction "1_1") (pintype "passive"))
      (node (ref "C58") (pin "1") (pinfunction "1_1") (pintype "passive"))
      (node (ref "C59") (pin "1") (pinfunction "1_1") (pintype "passive"))
      (node (ref "C60") (pin "1") (pinfunction "1_1") (pintype "passive"))
      (node (ref "C61") (pin "1") (pinfunction "1_1") (pintype "passive"))
      (node (ref "C62") (pin "1") (pinfunction "1_1") (pintype "passive"))
      (node (ref "C63") (pin "1") (pinfunction "1_1") (pintype "passive"))
      (node (ref "C64") (pin "1") (pinfunction "1_1") (pintype "passive"))
      (node (ref "C65") (pin "1") (pinfunction "1_1") (pintype "passive"))
      (node (ref "C66") (pin "1") (pinfunction "1_1") (pintype "passive"))
      (node (ref "C67") (pin "1") (pinfunction "1_1") (pintype "passive"))
      (node (ref "C68") (pin "1") (pinfunction "1_1") (pintype "passive"))
      (node (ref "C69") (pin "1") (pinfunction "1_1") (pintype "passive"))
      (node (ref "C70") (pin "1") (pinfunction "1_1") (pintype "passive"))
      (node (ref "C71") (pin "1") (pinfunction "1_1") (pintype "passive"))
      (node (ref "C72") (pin "1") (pinfunction "1_1") (pintype "passive"))
      (node (ref "C73") (pin "1") (pinfunction "1_1") (pintype "passive"))
      (node (ref "C74") (pin "1") (pinfunction "1_1") (pintype "passive"))
      (node (ref "C75") (pin "1") (pinfunction "1_1") (pintype "passive"))
      (node (ref "C76") (pin "1") (pinfunction "1_1") (pintype "passive"))
      (node (ref "C77") (pin "1") (pinfunction "1_1") (pintype "passive"))
      (node (ref "C78") (pin "1") (pinfunction "1_1") (pintype "passive"))
      (node (ref "LED00") (pin "2") (pinfunction "G_2") (pintype "passive"))
      (node (ref "LED01") (pin "2") (pinfunction "G_2") (pintype "passive"))
      (node (ref "LED02") (pin "2") (pinfunction "G_2") (pintype "passive"))
      (node (ref "LED03") (pin "2") (pinfunction "G_2") (pintype "passive"))
      (node (ref "LED07") (pin "2") (pinfunction "G_2") (pintype "passive"))
      (node (ref "LED08") (pin "2") (pinfunction "G_2") (pintype "passive"))
      (node (ref "LED09") (pin "2") (pinfunction "G_2") (pintype "passive"))
      (node (ref "LED0A") (pin "2") (pinfunction "G_2") (pintype "passive"))
      (node (ref "LED10") (pin "2") (pinfunction "G_2") (pintype "passive"))
      (node (ref "LED11") (pin "2") (pinfunction "G_2") (pintype "passive"))
      (node (ref "LED12") (pin "2") (pinfunction "G_2") (pintype "passive"))
      (node (ref "LED13") (pin "2") (pinfunction "G_2") (pintype "passive"))
      (node (ref "LED14") (pin "2") (pinfunction "G_2") (pintype "passive"))
      (node (ref "LED15") (pin "2") (pinfunction "G_2") (pintype "passive"))
      (node (ref "LED16") (pin "2") (pinfunction "G_2") (pintype "passive"))
      (node (ref "LED17") (pin "2") (pinfunction "G_2") (pintype "passive"))
      (node (ref "LED18") (pin "2") (pinfunction "G_2") (pintype "passive"))
      (node (ref "LED19") (pin "2") (pinfunction "G_2") (pintype "passive"))
      (node (ref "LED1A") (pin "2") (pinfunction "G_2") (pintype "passive"))
      (node (ref "LED20") (pin "2") (pinfunction "G_2") (pintype "passive"))
      (node (ref "LED21") (pin "2") (pinfunction "G_2") (pintype "passive"))
      (node (ref "LED22") (pin "2") (pinfunction "G_2") (pintype "passive"))
      (node (ref "LED23") (pin "2") (pinfunction "G_2") (pintype "passive"))
      (node (ref "LED24") (pin "2") (pinfunction "G_2") (pintype "passive"))
      (node (ref "LED25") (pin "2") (pinfunction "G_2") (pintype "passive"))
      (node (ref "LED26") (pin "2") (pinfunction "G_2") (pintype "passive"))
      (node (ref "LED27") (pin "2") (pinfunction "G_2") (pintype "passive"))
      (node (ref "LED28") (pin "2") (pinfunction "G_2") (pintype "passive"))
      (node (ref "LED29") (pin "2") (pinfunction "G_2") (pintype "passive"))
      (node (ref "LED2A") (pin "2") (pinfunction "G_2") (pintype "passive"))
      (node (ref "LED30") (pin "2") (pinfunction "G_2") (pintype "passive"))
      (node (ref "LED31") (pin "2") (pinfunction "G_2") (pintype "passive"))
      (node (ref "LED32") (pin "2") (pinfunction "G_2") (pintype "passive"))
      (node (ref "LED33") (pin "2") (pinfunction "G_2") (pintype "passive"))
      (node (ref "LED34") (pin "2") (pinfunction "G_2") (pintype "passive"))
      (node (ref "LED35") (pin "2") (pinfunction "G_2") (pintype "passive"))
      (node (ref "LED36") (pin "2") (pinfunction "G_2") (pintype "passive"))
      (node (ref "LED37") (pin "2") (pinfunction "G_2") (pintype "passive"))
      (node (ref "LED38") (pin "2") (pinfunction "G_2") (pintype "passive"))
      (node (ref "LED39") (pin "2") (pinfunction "G_2") (pintype "passive"))
      (node (ref "LED3A") (pin "2") (pinfunction "G_2") (pintype "passive"))
      (node (ref "LED40") (pin "2") (pinfunction "G_2") (pintype "passive"))
      (node (ref "LED41") (pin "2") (pinfunction "G_2") (pintype "passive"))
      (node (ref "LED42") (pin "2") (pinfunction "G_2") (pintype "passive"))
      (node (ref "LED43") (pin "2") (pinfunction "G_2") (pintype "passive"))
      (node (ref "LED44") (pin "2") (pinfunction "G_2") (pintype "passive"))
      (node (ref "LED45") (pin "2") (pinfunction "G_2") (pintype "passive"))
      (node (ref "LED46") (pin "2") (pinfunction "G_2") (pintype "passive"))
      (node (ref "LED47") (pin "2") (pinfunction "G_2") (pintype "passive"))
      (node (ref "LED48") (pin "2") (pinfunction "G_2") (pintype "passive"))
      (node (ref "LED49") (pin "2") (pinfunction "G_2") (pintype "passive"))
      (node (ref "LED4A") (pin "2") (pinfunction "G_2") (pintype "passive"))
      (node (ref "LED50") (pin "2") (pinfunction "G_2") (pintype "passive"))
      (node (ref "LED51") (pin "2") (pinfunction "G_2") (pintype "passive"))
      (node (ref "LED52") (pin "2") (pinfunction "G_2") (pintype "passive"))
      (node (ref "LED53") (pin "2") (pinfunction "G_2") (pintype "passive"))
      (node (ref "LED54") (pin "2") (pinfunction "G_2") (pintype "passive"))
      (node (ref "LED55") (pin "2") (pinfunction "G_2") (pintype "passive"))
      (node (ref "LED56") (pin "2") (pinfunction "G_2") (pintype "passive"))
      (node (ref "LED57") (pin "2") (pinfunction "G_2") (pintype "passive"))
      (node (ref "LED58") (pin "2") (pinfunction "G_2") (pintype "passive"))
      (node (ref "LED59") (pin "2") (pinfunction "G_2") (pintype "passive"))
      (node (ref "LED5A") (pin "2") (pinfunction "G_2") (pintype "passive"))
    )
    (net (code "4") (name "Net-(LED00-I)") (class "Default")
      (node (ref "LED00") (pin "3") (pinfunction "I_3") (pintype "passive"))
      (node (ref "LED01") (pin "1") (pinfunction "O_1") (pintype "passive"))
    )
    (net (code "5") (name "Net-(LED00-O)") (class "Default")
      (node (ref "LED00") (pin "1") (pinfunction "O_1") (pintype "passive"))
      (node (ref "LED10") (pin "3") (pinfunction "I_3") (pintype "passive"))
    )
    (net (code "6") (name "Net-(LED01-I)") (class "Default")
      (node (ref "LED01") (pin "3") (pinfunction "I_3") (pintype "passive"))
      (node (ref "LED02") (pin "1") (pinfunction "O_1") (pintype "passive"))
    )
    (net (code "7") (name "Net-(LED1A-O)") (class "Default")
      (node (ref "LED1A") (pin "1") (pinfunction "O_1") (pintype "passive"))
      (node (ref "LED2A") (pin "3") (pinfunction "I_3") (pintype "passive"))
    )
    (net (code "8") (name "Net-(LED02-I)") (class "Default")
      (node (ref "LED02") (pin "3") (pinfunction "I_3") (pintype "passive"))
      (node (ref "LED03") (pin "1") (pinfunction "O_1") (pintype "passive"))
    )
    (net (code "9") (name "Net-(LED03-I)") (class "Default")
      (node (ref "LED03") (pin "3") (pinfunction "I_3") (pintype "passive"))
      (node (ref "LED07") (pin "1") (pinfunction "O_1") (pintype "passive"))
    )
    (net (code "10") (name "Net-(LED3A-O)") (class "Default")
      (node (ref "LED3A") (pin "1") (pinfunction "O_1") (pintype "passive"))
      (node (ref "LED4A") (pin "3") (pinfunction "I_3") (pintype "passive"))
    )
    (net (code "11") (name "Net-(LED07-I)") (class "Default")
      (node (ref "LED07") (pin "3") (pinfunction "I_3") (pintype "passive"))
      (node (ref "LED08") (pin "1") (pinfunction "O_1") (pintype "passive"))
    )
    (net (code "12") (name "Net-(LED08-I)") (class "Default")
      (node (ref "LED08") (pin "3") (pinfunction "I_3") (pintype "passive"))
      (node (ref "LED09") (pin "1") (pinfunction "O_1") (pintype "passive"))
    )
    (net (code "13") (name "Net-(LED09-I)") (class "Default")
      (node (ref "LED09") (pin "3") (pinfunction "I_3") (pintype "passive"))
      (node (ref "LED0A") (pin "1") (pinfunction "O_1") (pintype "passive"))
    )
    (net (code "14") (name "Net-(LED10-O)") (class "Default")
      (node (ref "LED10") (pin "1") (pinfunction "O_1") (pintype "passive"))
      (node (ref "LED11") (pin "3") (pinfunction "I_3") (pintype "passive"))
    )
    (net (code "15") (name "Net-(LED11-O)") (class "Default")
      (node (ref "LED11") (pin "1") (pinfunction "O_1") (pintype "passive"))
      (node (ref "LED12") (pin "3") (pinfunction "I_3") (pintype "passive"))
    )
    (net (code "16") (name "Net-(LED12-O)") (class "Default")
      (node (ref "LED12") (pin "1") (pinfunction "O_1") (pintype "passive"))
      (node (ref "LED13") (pin "3") (pinfunction "I_3") (pintype "passive"))
    )
    (net (code "17") (name "Net-(LED13-O)") (class "Default")
      (node (ref "LED13") (pin "1") (pinfunction "O_1") (pintype "passive"))
      (node (ref "LED14") (pin "3") (pinfunction "I_3") (pintype "passive"))
    )
    (net (code "18") (name "Net-(LED14-O)") (class "Default")
      (node (ref "LED14") (pin "1") (pinfunction "O_1") (pintype "passive"))
      (node (ref "LED15") (pin "3") (pinfunction "I_3") (pintype "passive"))
    )
    (net (code "19") (name "Net-(LED15-O)") (class "Default")
      (node (ref "LED15") (pin "1") (pinfunction "O_1") (pintype "passive"))
      (node (ref "LED16") (pin "3") (pinfunction "I_3") (pintype "passive"))
    )
    (net (code "20") (name "Net-(LED16-O)") (class "Default")
      (node (ref "LED16") (pin "1") (pinfunction "O_1") (pintype "passive"))
      (node (ref "LED17") (pin "3") (pinfunction "I_3") (pintype "passive"))
    )
    (net (code "21") (name "Net-(LED17-O)") (class "Default")
      (node (ref "LED17") (pin "1") (pinfunction "O_1") (pintype "passive"))
      (node (ref "LED18") (pin "3") (pinfunction "I_3") (pintype "passive"))
    )
    (net (code "22") (name "Net-(LED18-O)") (class "Default")
      (node (ref "LED18") (pin "1") (pinfunction "O_1") (pintype "passive"))
      (node (ref "LED19") (pin "3") (pinfunction "I_3") (pintype "passive"))
    )
    (net (code "23") (name "Net-(LED19-O)") (class "Default")
      (node (ref "LED19") (pin "1") (pinfunction "O_1") (pintype "passive"))
      (node (ref "LED1A") (pin "3") (pinfunction "I_3") (pintype "passive"))
    )
    (net (code "24") (name "Net-(LED20-I)") (class "Default")
      (node (ref "LED20") (pin "3") (pinfunction "I_3") (pintype "passive"))
      (node (ref "LED21") (pin "1") (pinfunction "O_1") (pintype "passive"))
    )
    (net (code "25") (name "Net-(LED20-O)") (class "Default")
      (node (ref "LED20") (pin "1") (pinfunction "O_1") (pintype "passive"))
      (node (ref "LED30") (pin "3") (pinfunction "I_3") (pintype "passive"))
    )
    (net (code "26") (name "Net-(LED21-I)") (class "Default")
      (node (ref "LED21") (pin "3") (pinfunction "I_3") (pintype "passive"))
      (node (ref "LED22") (pin "1") (pinfunction "O_1") (pintype "passive"))
    )
    (net (code "27") (name "Net-(LED22-I)") (class "Default")
      (node (ref "LED22") (pin "3") (pinfunction "I_3") (pintype "passive"))
      (node (ref "LED23") (pin "1") (pinfunction "O_1") (pintype "passive"))
    )
    (net (code "28") (name "Net-(LED23-I)") (class "Default")
      (node (ref "LED23") (pin "3") (pinfunction "I_3") (pintype "passive"))
      (node (ref "LED24") (pin "1") (pinfunction "O_1") (pintype "passive"))
    )
    (net (code "29") (name "Net-(LED24-I)") (class "Default")
      (node (ref "LED24") (pin "3") (pinfunction "I_3") (pintype "passive"))
      (node (ref "LED25") (pin "1") (pinfunction "O_1") (pintype "passive"))
    )
    (net (code "30") (name "Net-(LED25-I)") (class "Default")
      (node (ref "LED25") (pin "3") (pinfunction "I_3") (pintype "passive"))
      (node (ref "LED26") (pin "1") (pinfunction "O_1") (pintype "passive"))
    )
    (net (code "31") (name "Net-(LED26-I)") (class "Default")
      (node (ref "LED26") (pin "3") (pinfunction "I_3") (pintype "passive"))
      (node (ref "LED27") (pin "1") (pinfunction "O_1") (pintype "passive"))
    )
    (net (code "32") (name "Net-(LED27-I)") (class "Default")
      (node (ref "LED27") (pin "3") (pinfunction "I_3") (pintype "passive"))
      (node (ref "LED28") (pin "1") (pinfunction "O_1") (pintype "passive"))
    )
    (net (code "33") (name "Net-(LED28-I)") (class "Default")
      (node (ref "LED28") (pin "3") (pinfunction "I_3") (pintype "passive"))
      (node (ref "LED29") (pin "1") (pinfunction "O_1") (pintype "passive"))
    )
    (net (code "34") (name "Net-(LED29-I)") (class "Default")
      (node (ref "LED29") (pin "3") (pinfunction "I_3") (pintype "passive"))
      (node (ref "LED2A") (pin "1") (pinfunction "O_1") (pintype "passive"))
    )
    (net (code "35") (name "Net-(LED30-O)") (class "Default")
      (node (ref "LED30") (pin "1") (pinfunction "O_1") (pintype "passive"))
      (node (ref "LED31") (pin "3") (pinfunction "I_3") (pintype "passive"))
    )
    (net (code "36") (name "Net-(LED31-O)") (class "Default")
      (node (ref "LED31") (pin "1") (pinfunction "O_1") (pintype "passive"))
      (node (ref "LED32") (pin "3") (pinfunction "I_3") (pintype "passive"))
    )
    (net (code "37") (name "Net-(LED32-O)") (class "Default")
      (node (ref "LED32") (pin "1") (pinfunction "O_1") (pintype "passive"))
      (node (ref "LED33") (pin "3") (pinfunction "I_3") (pintype "passive"))
    )
    (net (code "38") (name "Net-(LED33-O)") (class "Default")
      (node (ref "LED33") (pin "1") (pinfunction "O_1") (pintype "passive"))
      (node (ref "LED34") (pin "3") (pinfunction "I_3") (pintype "passive"))
    )
    (net (code "39") (name "Net-(LED34-O)") (class "Default")
      (node (ref "LED34") (pin "1") (pinfunction "O_1") (pintype "passive"))
      (node (ref "LED35") (pin "3") (pinfunction "I_3") (pintype "passive"))
    )
    (net (code "40") (name "Net-(LED35-O)") (class "Default")
      (node (ref "LED35") (pin "1") (pinfunction "O_1") (pintype "passive"))
      (node (ref "LED36") (pin "3") (pinfunction "I_3") (pintype "passive"))
    )
    (net (code "41") (name "Net-(LED36-O)") (class "Default")
      (node (ref "LED36") (pin "1") (pinfunction "O_1") (pintype "passive"))
      (node (ref "LED37") (pin "3") (pinfunction "I_3") (pintype "passive"))
    )
    (net (code "42") (name "Net-(LED37-O)") (class "Default")
      (node (ref "LED37") (pin "1") (pinfunction "O_1") (pintype "passive"))
      (node (ref "LED38") (pin "3") (pinfunction "I_3") (pintype "passive"))
    )
    (net (code "43") (name "Net-(LED38-O)") (class "Default")
      (node (ref "LED38") (pin "1") (pinfunction "O_1") (pintype "passive"))
      (node (ref "LED39") (pin "3") (pinfunction "I_3") (pintype "passive"))
    )
    (net (code "44") (name "Net-(LED39-O)") (class "Default")
      (node (ref "LED39") (pin "1") (pinfunction "O_1") (pintype "passive"))
      (node (ref "LED3A") (pin "3") (pinfunction "I_3") (pintype "passive"))
    )
    (net (code "45") (name "Net-(LED40-I)") (class "Default")
      (node (ref "LED40") (pin "3") (pinfunction "I_3") (pintype "passive"))
      (node (ref "LED41") (pin "1") (pinfunction "O_1") (pintype "passive"))
    )
    (net (code "46") (name "Net-(LED40-O)") (class "Default")
      (node (ref "LED40") (pin "1") (pinfunction "O_1") (pintype "passive"))
      (node (ref "LED50") (pin "3") (pinfunction "I_3") (pintype "passive"))
    )
    (net (code "47") (name "Net-(LED41-I)") (class "Default")
      (node (ref "LED41") (pin "3") (pinfunction "I_3") (pintype "passive"))
      (node (ref "LED42") (pin "1") (pinfunction "O_1") (pintype "passive"))
    )
    (net (code "48") (name "Net-(LED42-I)") (class "Default")
      (node (ref "LED42") (pin "3") (pinfunction "I_3") (pintype "passive"))
      (node (ref "LED43") (pin "1") (pinfunction "O_1") (pintype "passive"))
    )
    (net (code "49") (name "Net-(LED43-I)") (class "Default")
      (node (ref "LED43") (pin "3") (pinfunction "I_3") (pintype "passive"))
      (node (ref "LED44") (pin "1") (pinfunction "O_1") (pintype "passive"))
    )
    (net (code "50") (name "Net-(LED44-I)") (class "Default")
      (node (ref "LED44") (pin "3") (pinfunction "I_3") (pintype "passive"))
      (node (ref "LED45") (pin "1") (pinfunction "O_1") (pintype "passive"))
    )
    (net (code "51") (name "Net-(LED45-I)") (class "Default")
      (node (ref "LED45") (pin "3") (pinfunction "I_3") (pintype "passive"))
      (node (ref "LED46") (pin "1") (pinfunction "O_1") (pintype "passive"))
    )
    (net (code "52") (name "Net-(LED46-I)") (class "Default")
      (node (ref "LED46") (pin "3") (pinfunction "I_3") (pintype "passive"))
      (node (ref "LED47") (pin "1") (pinfunction "O_1") (pintype "passive"))
    )
    (net (code "53") (name "Net-(LED47-I)") (class "Default")
      (node (ref "LED47") (pin "3") (pinfunction "I_3") (pintype "passive"))
      (node (ref "LED48") (pin "1") (pinfunction "O_1") (pintype "passive"))
    )
    (net (code "54") (name "Net-(LED48-I)") (class "Default")
      (node (ref "LED48") (pin "3") (pinfunction "I_3") (pintype "passive"))
      (node (ref "LED49") (pin "1") (pinfunction "O_1") (pintype "passive"))
    )
    (net (code "55") (name "Net-(LED49-I)") (class "Default")
      (node (ref "LED49") (pin "3") (pinfunction "I_3") (pintype "passive"))
      (node (ref "LED4A") (pin "1") (pinfunction "O_1") (pintype "passive"))
    )
    (net (code "56") (name "Net-(LED50-O)") (class "Default")
      (node (ref "LED50") (pin "1") (pinfunction "O_1") (pintype "passive"))
      (node (ref "LED51") (pin "3") (pinfunction "I_3") (pintype "passive"))
    )
    (net (code "57") (name "Net-(LED51-O)") (class "Default")
      (node (ref "LED51") (pin "1") (pinfunction "O_1") (pintype "passive"))
      (node (ref "LED52") (pin "3") (pinfunction "I_3") (pintype "passive"))
    )
    (net (code "58") (name "Net-(LED52-O)") (class "Default")
      (node (ref "LED52") (pin "1") (pinfunction "O_1") (pintype "passive"))
      (node (ref "LED53") (pin "3") (pinfunction "I_3") (pintype "passive"))
    )
    (net (code "59") (name "Net-(LED53-O)") (class "Default")
      (node (ref "LED53") (pin "1") (pinfunction "O_1") (pintype "passive"))
      (node (ref "LED54") (pin "3") (pinfunction "I_3") (pintype "passive"))
    )
    (net (code "60") (name "Net-(LED54-O)") (class "Default")
      (node (ref "LED54") (pin "1") (pinfunction "O_1") (pintype "passive"))
      (node (ref "LED55") (pin "3") (pinfunction "I_3") (pintype "passive"))
    )
    (net (code "61") (name "Net-(LED55-O)") (class "Default")
      (node (ref "LED55") (pin "1") (pinfunction "O_1") (pintype "passive"))
      (node (ref "LED56") (pin "3") (pinfunction "I_3") (pintype "passive"))
    )
    (net (code "62") (name "Net-(LED56-O)") (class "Default")
      (node (ref "LED56") (pin "1") (pinfunction "O_1") (pintype "passive"))
      (node (ref "LED57") (pin "3") (pinfunction "I_3") (pintype "passive"))
    )
    (net (code "63") (name "Net-(LED57-O)") (class "Default")
      (node (ref "LED57") (pin "1") (pinfunction "O_1") (pintype "passive"))
      (node (ref "LED58") (pin "3") (pinfunction "I_3") (pintype "passive"))
    )
    (net (code "64") (name "Net-(LED58-O)") (class "Default")
      (node (ref "LED58") (pin "1") (pinfunction "O_1") (pintype "passive"))
      (node (ref "LED59") (pin "3") (pinfunction "I_3") (pintype "passive"))
    )
    (net (code "65") (name "Net-(LED59-O)") (class "Default")
      (node (ref "LED59") (pin "1") (pinfunction "O_1") (pintype "passive"))
      (node (ref "LED5A") (pin "3") (pinfunction "I_3") (pintype "passive"))
    )
    (net (code "66") (name "unconnected-(LED5A-O-Pad1)") (class "Default")
      (node (ref "LED5A") (pin "1") (pinfunction "O_1") (pintype "passive+no_connect"))
    )
  )
)
